# Computer.net
KiCad netlist of a schematic drawn in EasyEDA
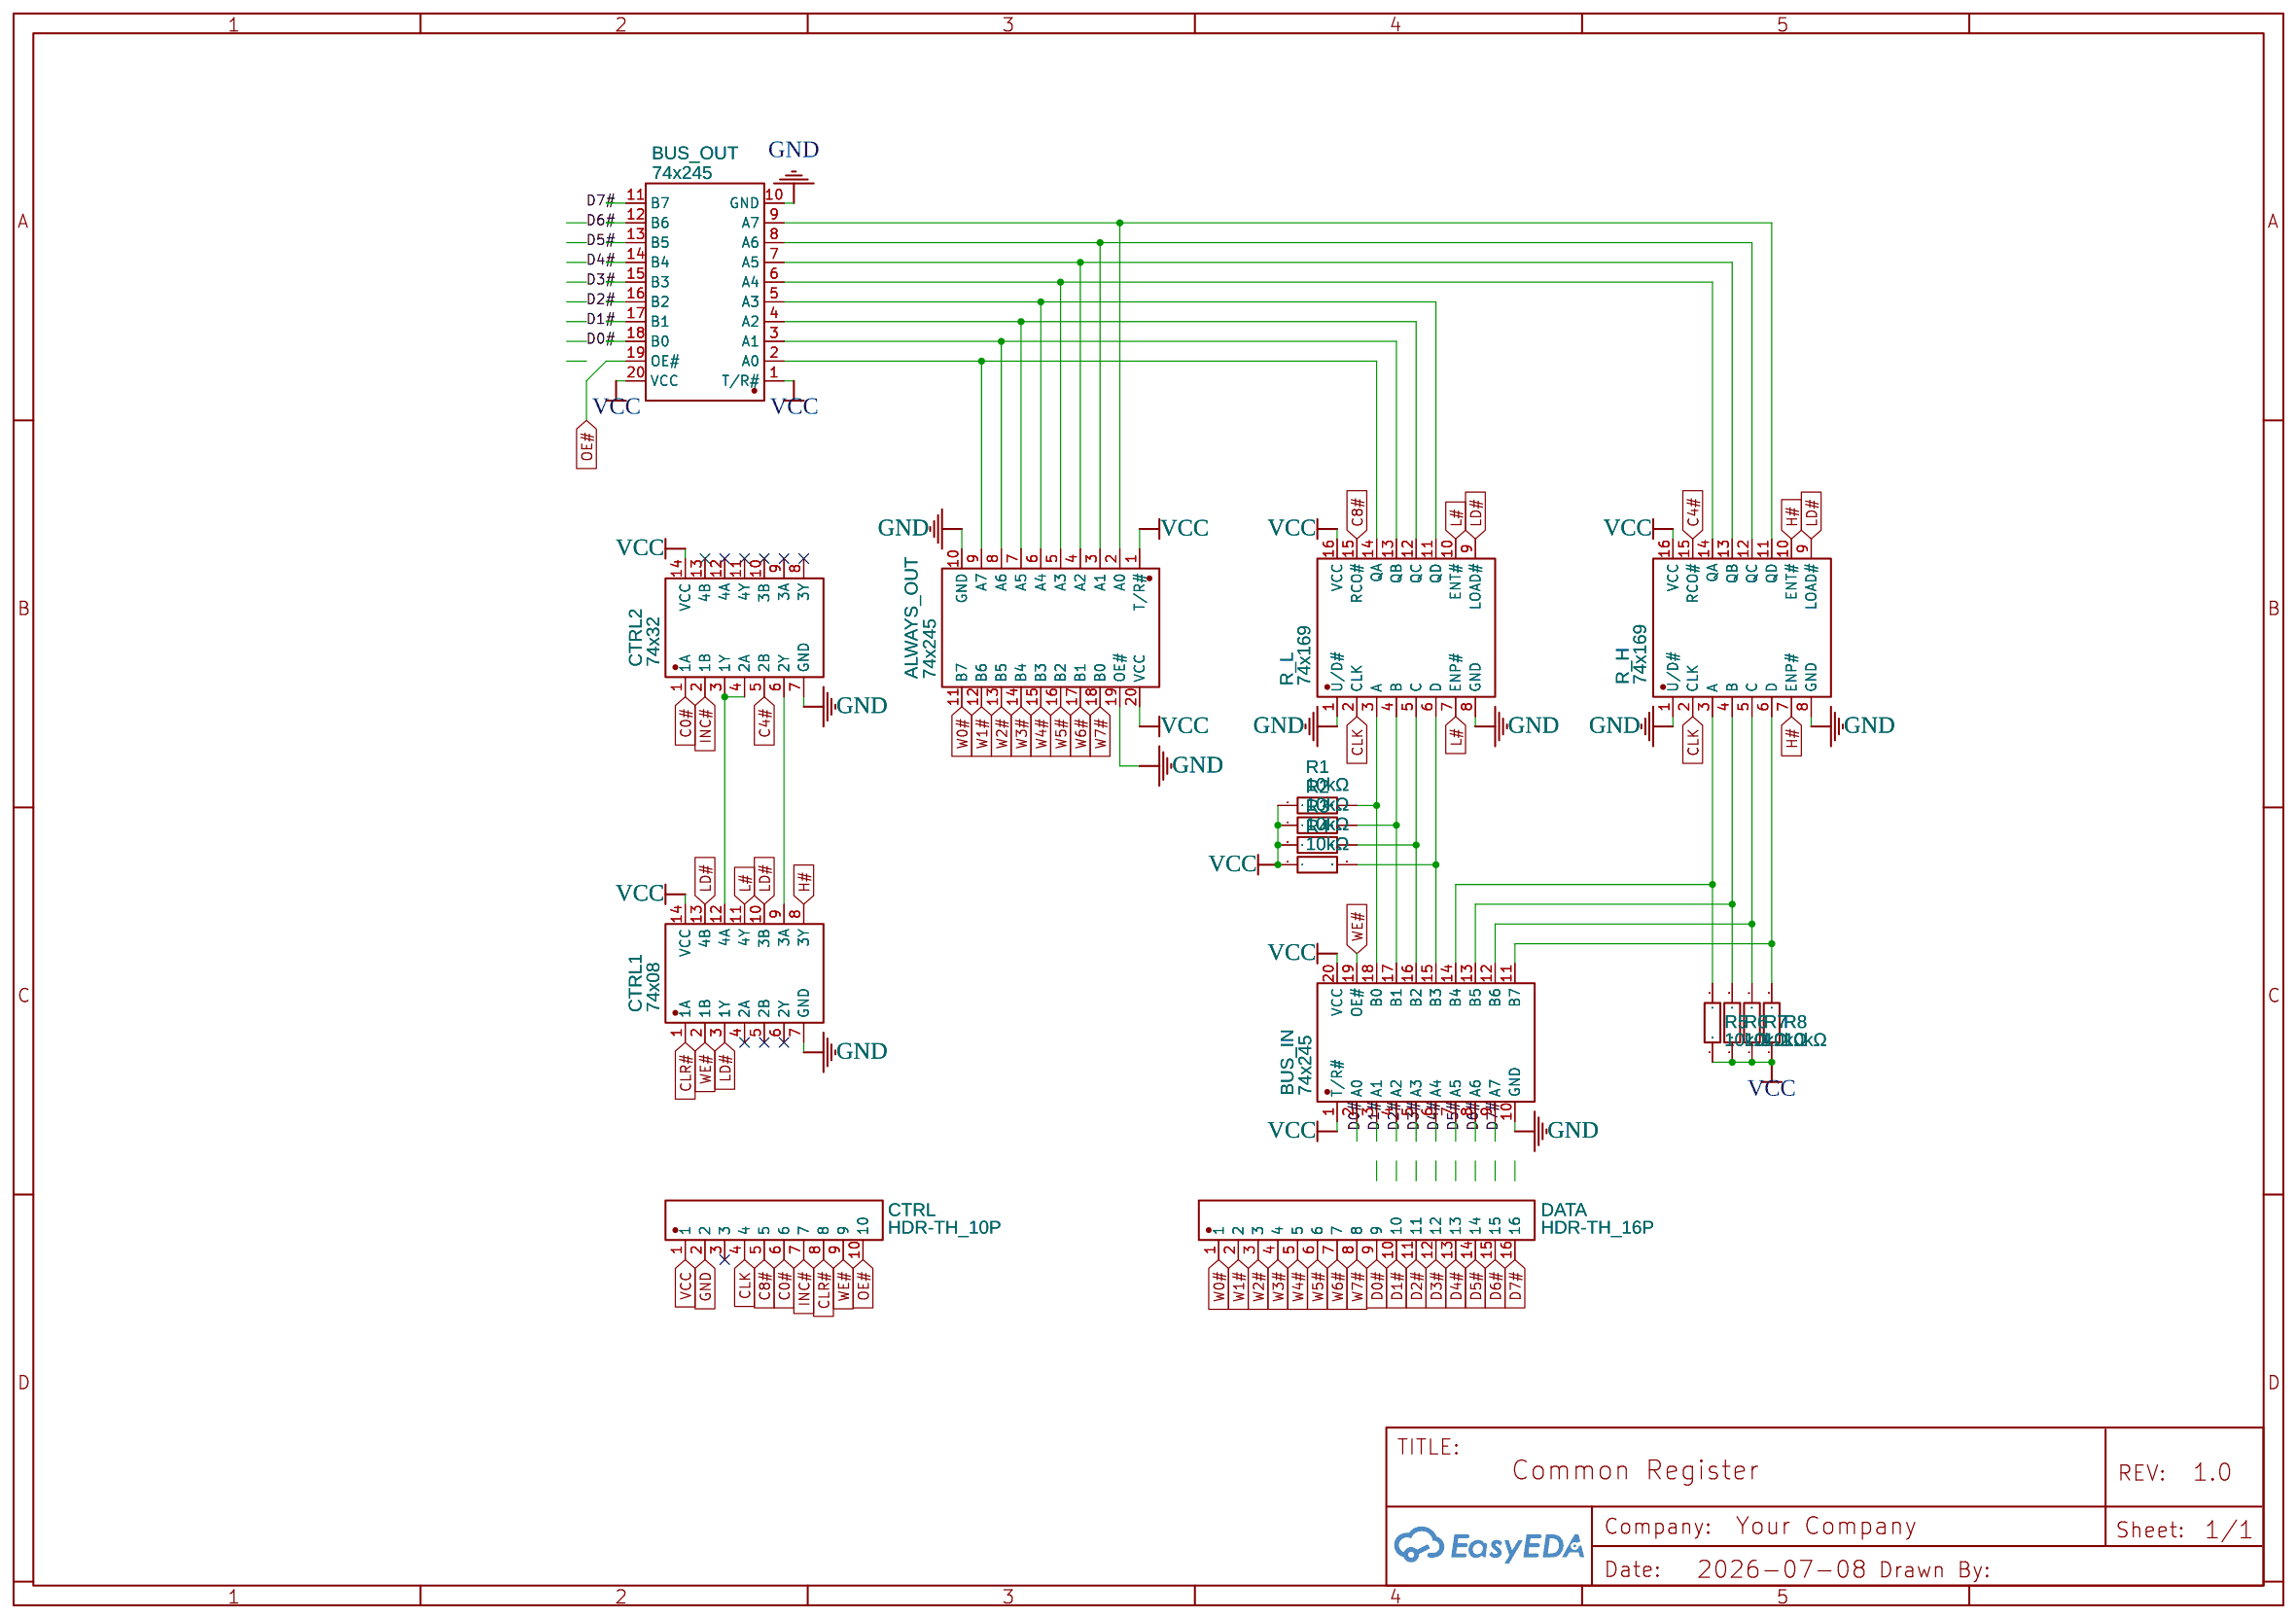
[diagram p0: schematic sheet]

(export (version "E")
  (design (tool "Eeschema 10.0.6"))
  (components
    (comp (ref "ALWAYS_OUT")
      (value "74x245")
      (fields (field (name "Manufacturer Part") "DM74LS245N") (field (name "Manufacturer") "onsemi(安森美)"))
      (libsource (lib "") (part "DM74LS245N"))
    )
    (comp (ref "BUS_IN")
      (value "74x245")
      (fields (field (name "Manufacturer Part") "DM74LS245N") (field (name "Manufacturer") "onsemi(安森美)"))
      (libsource (lib "") (part "DM74LS245N_2"))
    )
    (comp (ref "BUS_OUT")
      (value "74x245")
      (fields (field (name "Manufacturer Part") "DM74LS245N") (field (name "Manufacturer") "onsemi(安森美)"))
      (libsource (lib "") (part "DM74LS245N_1"))
    )
    (comp (ref "CTRL")
      (value "HDR-TH_10P")
      (fields
        (field (name "Manufacturer Part") "B25410120-10PB0513-H25A60")
        (field (name "Manufacturer") "HMTCONN(华明通)")
      )
      (libsource (lib "") (part "B25410120-10PB0513-H25A60"))
    )
    (comp (ref "CTRL1")
      (value "74x08")
      (fields (field (name "Manufacturer Part") "SN74LS08N") (field (name "Manufacturer") "TI(德州仪器)"))
      (libsource (lib "") (part "SN74LS08N"))
    )
    (comp (ref "CTRL2")
      (value "74x32")
      (fields (field (name "Manufacturer Part") "SN74LS32N") (field (name "Manufacturer") "TI(德州仪器)"))
      (libsource (lib "") (part "SN74LS32N"))
    )
    (comp (ref "DATA")
      (value "HDR-TH_16P")
      (fields
        (field (name "Manufacturer Part") "ZX-PZ1.27-1-16PZZ")
        (field (name "Manufacturer") "Megastar(兆星)")
      )
      (libsource (lib "") (part "ZX-PZ1.27-1-16PZZ"))
    )
    (comp (ref "R1")
      (value "10kΩ")
      (fields (field (name "Manufacturer Part") "MF1/4W-10KΩ±1% T") (field (name "Manufacturer") "CCO(千志电子)"))
      (libsource (lib "") (part "MF1/4W-10KΩ±1% T52_1"))
    )
    (comp (ref "R2")
      (value "10kΩ")
      (fields (field (name "Manufacturer Part") "MF1/4W-10KΩ±1% T") (field (name "Manufacturer") "CCO(千志电子)"))
      (libsource (lib "") (part "MF1/4W-10KΩ±1% T52_1"))
    )
    (comp (ref "R3")
      (value "10kΩ")
      (fields (field (name "Manufacturer Part") "MF1/4W-10KΩ±1% T") (field (name "Manufacturer") "CCO(千志电子)"))
      (libsource (lib "") (part "MF1/4W-10KΩ±1% T52_1"))
    )
    (comp (ref "R4")
      (value "10kΩ")
      (fields (field (name "Manufacturer Part") "MF1/4W-10KΩ±1% T") (field (name "Manufacturer") "CCO(千志电子)"))
      (libsource (lib "") (part "MF1/4W-10KΩ±1% T52_1"))
    )
    (comp (ref "R5")
      (value "10kΩ")
      (fields (field (name "Manufacturer Part") "MF1/4W-10KΩ±1% T") (field (name "Manufacturer") "CCO(千志电子)"))
      (libsource (lib "") (part "MF1/4W-10KΩ±1% T52"))
    )
    (comp (ref "R6")
      (value "10kΩ")
      (fields (field (name "Manufacturer Part") "MF1/4W-10KΩ±1% T") (field (name "Manufacturer") "CCO(千志电子)"))
      (libsource (lib "") (part "MF1/4W-10KΩ±1% T52"))
    )
    (comp (ref "R7")
      (value "10kΩ")
      (fields (field (name "Manufacturer Part") "MF1/4W-10KΩ±1% T") (field (name "Manufacturer") "CCO(千志电子)"))
      (libsource (lib "") (part "MF1/4W-10KΩ±1% T52"))
    )
    (comp (ref "R8")
      (value "10kΩ")
      (fields (field (name "Manufacturer Part") "MF1/4W-10KΩ±1% T") (field (name "Manufacturer") "CCO(千志电子)"))
      (libsource (lib "") (part "MF1/4W-10KΩ±1% T52"))
    )
    (comp (ref "R_H")
      (value "74x169")
      (fields (field (name "Manufacturer Part") "SN74LS169BN") (field (name "Manufacturer") "TI(德州仪器)"))
      (libsource (lib "") (part "SN74LS169BN"))
    )
    (comp (ref "R_L")
      (value "74x169")
      (fields (field (name "Manufacturer Part") "SN74LS169BN") (field (name "Manufacturer") "TI(德州仪器)"))
      (libsource (lib "") (part "SN74LS169BN_1"))
    )
  )
  (nets
    (net (code "1") (name "C0#") (class "Default")
      (node (ref "CTRL") (pin "6") (pinfunction "6_6") (pintype "unspecified"))
      (node (ref "CTRL2") (pin "1") (pinfunction "1A_1") (pintype "unspecified"))
    )
    (net (code "2") (name "C4#") (class "Default")
      (node (ref "CTRL2") (pin "5") (pinfunction "2B_5") (pintype "unspecified"))
      (node (ref "R_H") (pin "15") (pinfunction "RCO#_15") (pintype "unspecified"))
    )
    (net (code "3") (name "C8#") (class "Default")
      (node (ref "CTRL") (pin "5") (pinfunction "5_5") (pintype "unspecified"))
      (node (ref "R_L") (pin "15") (pinfunction "RCO#_15") (pintype "unspecified"))
    )
    (net (code "4") (name "CLK") (class "Default")
      (node (ref "CTRL") (pin "4") (pinfunction "4_4") (pintype "unspecified"))
      (node (ref "R_H") (pin "2") (pinfunction "CLK_2") (pintype "unspecified"))
      (node (ref "R_L") (pin "2") (pinfunction "CLK_2") (pintype "unspecified"))
    )
    (net (code "5") (name "CLR#") (class "Default")
      (node (ref "CTRL") (pin "8") (pinfunction "8_8") (pintype "unspecified"))
      (node (ref "CTRL1") (pin "1") (pinfunction "1A_1") (pintype "unspecified"))
    )
    (net (code "6") (name "D0#") (class "Default")
      (node (ref "BUS_IN") (pin "2") (pinfunction "A0_2") (pintype "unspecified"))
      (node (ref "BUS_OUT") (pin "18") (pinfunction "B0_18") (pintype "unspecified"))
      (node (ref "DATA") (pin "9") (pinfunction "9_9") (pintype "unspecified"))
    )
    (net (code "7") (name "D1#") (class "Default")
      (node (ref "BUS_IN") (pin "3") (pinfunction "A1_3") (pintype "unspecified"))
      (node (ref "BUS_OUT") (pin "17") (pinfunction "B1_17") (pintype "unspecified"))
      (node (ref "DATA") (pin "10") (pinfunction "10_10") (pintype "unspecified"))
    )
    (net (code "8") (name "D2#") (class "Default")
      (node (ref "BUS_IN") (pin "4") (pinfunction "A2_4") (pintype "unspecified"))
      (node (ref "BUS_OUT") (pin "16") (pinfunction "B2_16") (pintype "unspecified"))
      (node (ref "DATA") (pin "11") (pinfunction "11_11") (pintype "unspecified"))
    )
    (net (code "9") (name "D3#") (class "Default")
      (node (ref "BUS_IN") (pin "5") (pinfunction "A3_5") (pintype "unspecified"))
      (node (ref "BUS_OUT") (pin "15") (pinfunction "B3_15") (pintype "unspecified"))
      (node (ref "DATA") (pin "12") (pinfunction "12_12") (pintype "unspecified"))
    )
    (net (code "10") (name "D4#") (class "Default")
      (node (ref "BUS_IN") (pin "6") (pinfunction "A4_6") (pintype "unspecified"))
      (node (ref "BUS_OUT") (pin "14") (pinfunction "B4_14") (pintype "unspecified"))
      (node (ref "DATA") (pin "13") (pinfunction "13_13") (pintype "unspecified"))
    )
    (net (code "11") (name "D5#") (class "Default")
      (node (ref "BUS_IN") (pin "7") (pinfunction "A5_7") (pintype "unspecified"))
      (node (ref "BUS_OUT") (pin "13") (pinfunction "B5_13") (pintype "unspecified"))
      (node (ref "DATA") (pin "14") (pinfunction "14_14") (pintype "unspecified"))
    )
    (net (code "12") (name "D6#") (class "Default")
      (node (ref "BUS_IN") (pin "8") (pinfunction "A6_8") (pintype "unspecified"))
      (node (ref "BUS_OUT") (pin "12") (pinfunction "B6_12") (pintype "unspecified"))
      (node (ref "DATA") (pin "15") (pinfunction "15_15") (pintype "unspecified"))
    )
    (net (code "13") (name "D7#") (class "Default")
      (node (ref "BUS_IN") (pin "9") (pinfunction "A7_9") (pintype "unspecified"))
      (node (ref "BUS_OUT") (pin "11") (pinfunction "B7_11") (pintype "unspecified"))
      (node (ref "DATA") (pin "16") (pinfunction "16_16") (pintype "unspecified"))
    )
    (net (code "14") (name "GND") (class "Default")
      (node (ref "ALWAYS_OUT") (pin "10") (pinfunction "GND_10") (pintype "unspecified"))
      (node (ref "ALWAYS_OUT") (pin "19") (pinfunction "OE#_19") (pintype "unspecified"))
      (node (ref "BUS_IN") (pin "10") (pinfunction "GND_10") (pintype "unspecified"))
      (node (ref "BUS_OUT") (pin "10") (pinfunction "GND_10") (pintype "unspecified"))
      (node (ref "CTRL") (pin "2") (pinfunction "2_2") (pintype "unspecified"))
      (node (ref "CTRL1") (pin "7") (pinfunction "GND_7") (pintype "unspecified"))
      (node (ref "CTRL2") (pin "7") (pinfunction "GND_7") (pintype "unspecified"))
      (node (ref "R_H") (pin "1") (pinfunction "U/D#_1") (pintype "unspecified"))
      (node (ref "R_H") (pin "8") (pinfunction "GND_8") (pintype "unspecified"))
      (node (ref "R_L") (pin "1") (pinfunction "U/D#_1") (pintype "unspecified"))
      (node (ref "R_L") (pin "8") (pinfunction "GND_8") (pintype "unspecified"))
    )
    (net (code "15") (name "H#") (class "Default")
      (node (ref "CTRL1") (pin "8") (pinfunction "3Y_8") (pintype "unspecified"))
      (node (ref "R_H") (pin "10") (pinfunction "ENT#_10") (pintype "unspecified"))
      (node (ref "R_H") (pin "7") (pinfunction "ENP#_7") (pintype "unspecified"))
    )
    (net (code "16") (name "INC#") (class "Default")
      (node (ref "CTRL") (pin "7") (pinfunction "7_7") (pintype "unspecified"))
      (node (ref "CTRL2") (pin "2") (pinfunction "1B_2") (pintype "unspecified"))
    )
    (net (code "17") (name "L#") (class "Default")
      (node (ref "CTRL1") (pin "11") (pinfunction "4Y_11") (pintype "unspecified"))
      (node (ref "R_L") (pin "10") (pinfunction "ENT#_10") (pintype "unspecified"))
      (node (ref "R_L") (pin "7") (pinfunction "ENP#_7") (pintype "unspecified"))
    )
    (net (code "18") (name "LD#") (class "Default")
      (node (ref "CTRL1") (pin "10") (pinfunction "3B_10") (pintype "unspecified"))
      (node (ref "CTRL1") (pin "13") (pinfunction "4B_13") (pintype "unspecified"))
      (node (ref "CTRL1") (pin "3") (pinfunction "1Y_3") (pintype "unspecified"))
      (node (ref "R_H") (pin "9") (pinfunction "LOAD#_9") (pintype "unspecified"))
      (node (ref "R_L") (pin "9") (pinfunction "LOAD#_9") (pintype "unspecified"))
    )
    (net (code "19") (name "Net-(ALWAYS_OUT-A0)") (class "Default")
      (node (ref "ALWAYS_OUT") (pin "2") (pinfunction "A0_2") (pintype "unspecified"))
      (node (ref "BUS_OUT") (pin "9") (pinfunction "A7_9") (pintype "unspecified"))
      (node (ref "R_H") (pin "11") (pinfunction "QD_11") (pintype "unspecified"))
    )
    (net (code "20") (name "Net-(ALWAYS_OUT-A1)") (class "Default")
      (node (ref "ALWAYS_OUT") (pin "3") (pinfunction "A1_3") (pintype "unspecified"))
      (node (ref "BUS_OUT") (pin "8") (pinfunction "A6_8") (pintype "unspecified"))
      (node (ref "R_H") (pin "12") (pinfunction "QC_12") (pintype "unspecified"))
    )
    (net (code "21") (name "Net-(ALWAYS_OUT-A2)") (class "Default")
      (node (ref "ALWAYS_OUT") (pin "4") (pinfunction "A2_4") (pintype "unspecified"))
      (node (ref "BUS_OUT") (pin "7") (pinfunction "A5_7") (pintype "unspecified"))
      (node (ref "R_H") (pin "13") (pinfunction "QB_13") (pintype "unspecified"))
    )
    (net (code "22") (name "Net-(ALWAYS_OUT-A3)") (class "Default")
      (node (ref "ALWAYS_OUT") (pin "5") (pinfunction "A3_5") (pintype "unspecified"))
      (node (ref "BUS_OUT") (pin "6") (pinfunction "A4_6") (pintype "unspecified"))
      (node (ref "R_H") (pin "14") (pinfunction "QA_14") (pintype "unspecified"))
    )
    (net (code "23") (name "Net-(ALWAYS_OUT-A4)") (class "Default")
      (node (ref "ALWAYS_OUT") (pin "6") (pinfunction "A4_6") (pintype "unspecified"))
      (node (ref "BUS_OUT") (pin "5") (pinfunction "A3_5") (pintype "unspecified"))
      (node (ref "R_L") (pin "11") (pinfunction "QD_11") (pintype "unspecified"))
    )
    (net (code "24") (name "Net-(ALWAYS_OUT-A5)") (class "Default")
      (node (ref "ALWAYS_OUT") (pin "7") (pinfunction "A5_7") (pintype "unspecified"))
      (node (ref "BUS_OUT") (pin "4") (pinfunction "A2_4") (pintype "unspecified"))
      (node (ref "R_L") (pin "12") (pinfunction "QC_12") (pintype "unspecified"))
    )
    (net (code "25") (name "Net-(ALWAYS_OUT-A6)") (class "Default")
      (node (ref "ALWAYS_OUT") (pin "8") (pinfunction "A6_8") (pintype "unspecified"))
      (node (ref "BUS_OUT") (pin "3") (pinfunction "A1_3") (pintype "unspecified"))
      (node (ref "R_L") (pin "13") (pinfunction "QB_13") (pintype "unspecified"))
    )
    (net (code "26") (name "Net-(ALWAYS_OUT-A7)") (class "Default")
      (node (ref "ALWAYS_OUT") (pin "9") (pinfunction "A7_9") (pintype "unspecified"))
      (node (ref "BUS_OUT") (pin "2") (pinfunction "A0_2") (pintype "unspecified"))
      (node (ref "R_L") (pin "14") (pinfunction "QA_14") (pintype "unspecified"))
    )
    (net (code "27") (name "Net-(BUS_IN-B0)") (class "Default")
      (node (ref "BUS_IN") (pin "18") (pinfunction "B0_18") (pintype "unspecified"))
      (node (ref "R1") (pin "2") (pinfunction "2_2") (pintype "unspecified"))
      (node (ref "R_L") (pin "3") (pinfunction "A_3") (pintype "unspecified"))
    )
    (net (code "28") (name "Net-(BUS_IN-B1)") (class "Default")
      (node (ref "BUS_IN") (pin "17") (pinfunction "B1_17") (pintype "unspecified"))
      (node (ref "R2") (pin "2") (pinfunction "2_2") (pintype "unspecified"))
      (node (ref "R_L") (pin "4") (pinfunction "B_4") (pintype "unspecified"))
    )
    (net (code "29") (name "Net-(BUS_IN-B2)") (class "Default")
      (node (ref "BUS_IN") (pin "16") (pinfunction "B2_16") (pintype "unspecified"))
      (node (ref "R3") (pin "2") (pinfunction "2_2") (pintype "unspecified"))
      (node (ref "R_L") (pin "5") (pinfunction "C_5") (pintype "unspecified"))
    )
    (net (code "30") (name "Net-(BUS_IN-B3)") (class "Default")
      (node (ref "BUS_IN") (pin "15") (pinfunction "B3_15") (pintype "unspecified"))
      (node (ref "R4") (pin "2") (pinfunction "2_2") (pintype "unspecified"))
      (node (ref "R_L") (pin "6") (pinfunction "D_6") (pintype "unspecified"))
    )
    (net (code "31") (name "Net-(BUS_IN-B4)") (class "Default")
      (node (ref "BUS_IN") (pin "14") (pinfunction "B4_14") (pintype "unspecified"))
      (node (ref "R5") (pin "2") (pinfunction "2_2") (pintype "unspecified"))
      (node (ref "R_H") (pin "3") (pinfunction "A_3") (pintype "unspecified"))
    )
    (net (code "32") (name "Net-(BUS_IN-B5)") (class "Default")
      (node (ref "BUS_IN") (pin "13") (pinfunction "B5_13") (pintype "unspecified"))
      (node (ref "R6") (pin "2") (pinfunction "2_2") (pintype "unspecified"))
      (node (ref "R_H") (pin "4") (pinfunction "B_4") (pintype "unspecified"))
    )
    (net (code "33") (name "Net-(BUS_IN-B6)") (class "Default")
      (node (ref "BUS_IN") (pin "12") (pinfunction "B6_12") (pintype "unspecified"))
      (node (ref "R7") (pin "2") (pinfunction "2_2") (pintype "unspecified"))
      (node (ref "R_H") (pin "5") (pinfunction "C_5") (pintype "unspecified"))
    )
    (net (code "34") (name "Net-(BUS_IN-B7)") (class "Default")
      (node (ref "BUS_IN") (pin "11") (pinfunction "B7_11") (pintype "unspecified"))
      (node (ref "R8") (pin "2") (pinfunction "2_2") (pintype "unspecified"))
      (node (ref "R_H") (pin "6") (pinfunction "D_6") (pintype "unspecified"))
    )
    (net (code "35") (name "Net-(CTRL1-3A)") (class "Default")
      (node (ref "CTRL1") (pin "9") (pinfunction "3A_9") (pintype "unspecified"))
      (node (ref "CTRL2") (pin "6") (pinfunction "2Y_6") (pintype "unspecified"))
    )
    (net (code "36") (name "Net-(CTRL1-4A)") (class "Default")
      (node (ref "CTRL1") (pin "12") (pinfunction "4A_12") (pintype "unspecified"))
      (node (ref "CTRL2") (pin "3") (pinfunction "1Y_3") (pintype "unspecified"))
      (node (ref "CTRL2") (pin "4") (pinfunction "2A_4") (pintype "unspecified"))
    )
    (net (code "37") (name "OE#") (class "Default")
      (node (ref "BUS_OUT") (pin "19") (pinfunction "OE#_19") (pintype "unspecified"))
      (node (ref "CTRL") (pin "10") (pinfunction "10_10") (pintype "unspecified"))
    )
    (net (code "38") (name "VCC") (class "Default")
      (node (ref "ALWAYS_OUT") (pin "1") (pinfunction "T/R#_1") (pintype "unspecified"))
      (node (ref "ALWAYS_OUT") (pin "20") (pinfunction "VCC_20") (pintype "unspecified"))
      (node (ref "BUS_IN") (pin "1") (pinfunction "T/R#_1") (pintype "unspecified"))
      (node (ref "BUS_IN") (pin "20") (pinfunction "VCC_20") (pintype "unspecified"))
      (node (ref "BUS_OUT") (pin "1") (pinfunction "T/R#_1") (pintype "unspecified"))
      (node (ref "BUS_OUT") (pin "20") (pinfunction "VCC_20") (pintype "unspecified"))
      (node (ref "CTRL") (pin "1") (pinfunction "1_1") (pintype "unspecified"))
      (node (ref "CTRL1") (pin "14") (pinfunction "VCC_14") (pintype "unspecified"))
      (node (ref "CTRL2") (pin "14") (pinfunction "VCC_14") (pintype "unspecified"))
      (node (ref "R1") (pin "1") (pinfunction "1_1") (pintype "unspecified"))
      (node (ref "R2") (pin "1") (pinfunction "1_1") (pintype "unspecified"))
      (node (ref "R3") (pin "1") (pinfunction "1_1") (pintype "unspecified"))
      (node (ref "R4") (pin "1") (pinfunction "1_1") (pintype "unspecified"))
      (node (ref "R5") (pin "1") (pinfunction "1_1") (pintype "unspecified"))
      (node (ref "R6") (pin "1") (pinfunction "1_1") (pintype "unspecified"))
      (node (ref "R7") (pin "1") (pinfunction "1_1") (pintype "unspecified"))
      (node (ref "R8") (pin "1") (pinfunction "1_1") (pintype "unspecified"))
      (node (ref "R_H") (pin "16") (pinfunction "VCC_16") (pintype "unspecified"))
      (node (ref "R_L") (pin "16") (pinfunction "VCC_16") (pintype "unspecified"))
    )
    (net (code "39") (name "W0#") (class "Default")
      (node (ref "ALWAYS_OUT") (pin "11") (pinfunction "B7_11") (pintype "unspecified"))
      (node (ref "DATA") (pin "1") (pinfunction "1_1") (pintype "unspecified"))
    )
    (net (code "40") (name "W1#") (class "Default")
      (node (ref "ALWAYS_OUT") (pin "12") (pinfunction "B6_12") (pintype "unspecified"))
      (node (ref "DATA") (pin "2") (pinfunction "2_2") (pintype "unspecified"))
    )
    (net (code "41") (name "W2#") (class "Default")
      (node (ref "ALWAYS_OUT") (pin "13") (pinfunction "B5_13") (pintype "unspecified"))
      (node (ref "DATA") (pin "3") (pinfunction "3_3") (pintype "unspecified"))
    )
    (net (code "42") (name "W3#") (class "Default")
      (node (ref "ALWAYS_OUT") (pin "14") (pinfunction "B4_14") (pintype "unspecified"))
      (node (ref "DATA") (pin "4") (pinfunction "4_4") (pintype "unspecified"))
    )
    (net (code "43") (name "W4#") (class "Default")
      (node (ref "ALWAYS_OUT") (pin "15") (pinfunction "B3_15") (pintype "unspecified"))
      (node (ref "DATA") (pin "5") (pinfunction "5_5") (pintype "unspecified"))
    )
    (net (code "44") (name "W5#") (class "Default")
      (node (ref "ALWAYS_OUT") (pin "16") (pinfunction "B2_16") (pintype "unspecified"))
      (node (ref "DATA") (pin "6") (pinfunction "6_6") (pintype "unspecified"))
    )
    (net (code "45") (name "W6#") (class "Default")
      (node (ref "ALWAYS_OUT") (pin "17") (pinfunction "B1_17") (pintype "unspecified"))
      (node (ref "DATA") (pin "7") (pinfunction "7_7") (pintype "unspecified"))
    )
    (net (code "46") (name "W7#") (class "Default")
      (node (ref "ALWAYS_OUT") (pin "18") (pinfunction "B0_18") (pintype "unspecified"))
      (node (ref "DATA") (pin "8") (pinfunction "8_8") (pintype "unspecified"))
    )
    (net (code "47") (name "WE#") (class "Default")
      (node (ref "BUS_IN") (pin "19") (pinfunction "OE#_19") (pintype "unspecified"))
      (node (ref "CTRL") (pin "9") (pinfunction "9_9") (pintype "unspecified"))
      (node (ref "CTRL1") (pin "2") (pinfunction "1B_2") (pintype "unspecified"))
    )
    (net (code "48") (name "unconnected-(CTRL-Pad3)") (class "Default")
      (node (ref "CTRL") (pin "3") (pinfunction "3_3") (pintype "unspecified+no_connect"))
    )
    (net (code "49") (name "unconnected-(CTRL1-2A-Pad4)") (class "Default")
      (node (ref "CTRL1") (pin "4") (pinfunction "2A_4") (pintype "unspecified+no_connect"))
    )
    (net (code "50") (name "unconnected-(CTRL1-2B-Pad5)") (class "Default")
      (node (ref "CTRL1") (pin "5") (pinfunction "2B_5") (pintype "unspecified+no_connect"))
    )
    (net (code "51") (name "unconnected-(CTRL1-2Y-Pad6)") (class "Default")
      (node (ref "CTRL1") (pin "6") (pinfunction "2Y_6") (pintype "unspecified+no_connect"))
    )
    (net (code "52") (name "unconnected-(CTRL2-3A-Pad9)") (class "Default")
      (node (ref "CTRL2") (pin "9") (pinfunction "3A_9") (pintype "unspecified+no_connect"))
    )
    (net (code "53") (name "unconnected-(CTRL2-3B-Pad10)") (class "Default")
      (node (ref "CTRL2") (pin "10") (pinfunction "3B_10") (pintype "unspecified+no_connect"))
    )
    (net (code "54") (name "unconnected-(CTRL2-3Y-Pad8)") (class "Default")
      (node (ref "CTRL2") (pin "8") (pinfunction "3Y_8") (pintype "unspecified+no_connect"))
    )
    (net (code "55") (name "unconnected-(CTRL2-4A-Pad12)") (class "Default")
      (node (ref "CTRL2") (pin "12") (pinfunction "4A_12") (pintype "unspecified+no_connect"))
    )
    (net (code "56") (name "unconnected-(CTRL2-4B-Pad13)") (class "Default")
      (node (ref "CTRL2") (pin "13") (pinfunction "4B_13") (pintype "unspecified+no_connect"))
    )
    (net (code "57") (name "unconnected-(CTRL2-4Y-Pad11)") (class "Default")
      (node (ref "CTRL2") (pin "11") (pinfunction "4Y_11") (pintype "unspecified+no_connect"))
    )
  )
)
